# SUP_2_5_FMC.net
KiCad netlist of a schematic drawn in Altium Designer
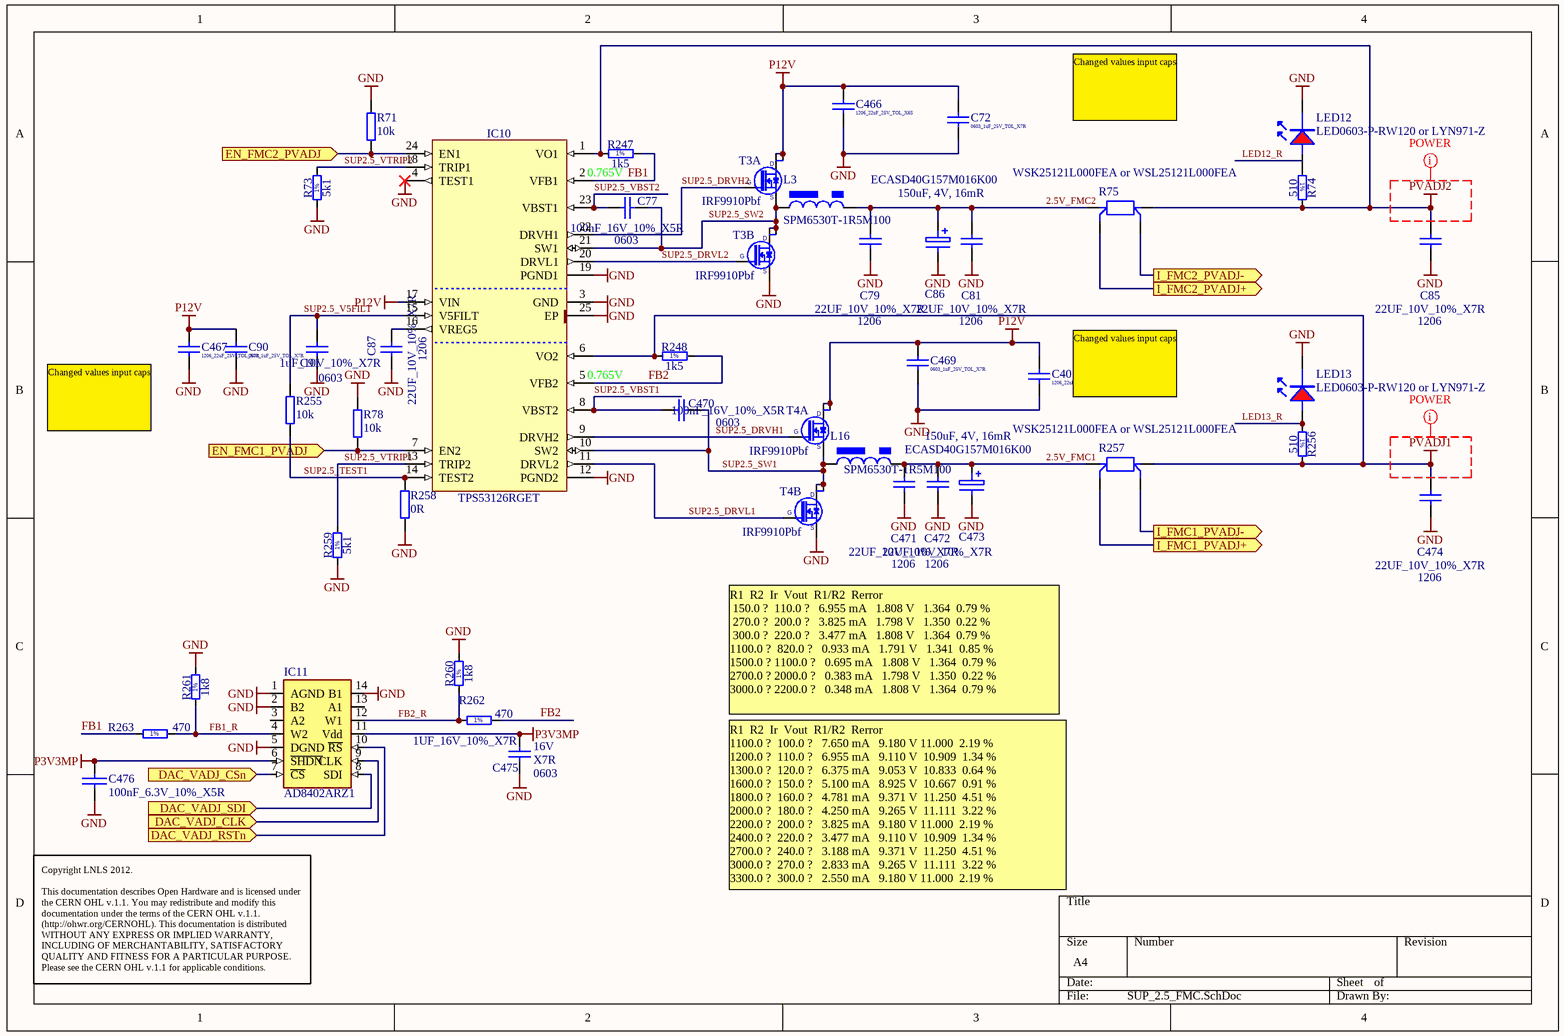
[diagram p0: SUP_2.5_FMC.SchDoc]

(export (version "E")
  (design (tool "Eeschema 10.0.6"))
  (components
    (comp (ref "C40")
      (value "1206_22uF_25V_TOL_X6S")
      (footprint "CAPC3225X140N")
      (fields (field (name "PART NUMBER") "Ceramic_1206"))
      (libsource (lib "Capacitors") (part "Capacitor"))
    )
    (comp (ref "C72")
      (value "0603_1uF_25V_TOL_X7R")
      (footprint "CAPC1608X90N")
      (fields (field (name "PART NUMBER") "Ceramic_0603"))
      (libsource (lib "Capacitors") (part "Capacitor"))
    )
    (comp (ref "C77")
      (value "100nF_16V_10%_X5R")
      (footprint "0402C")
      (description "Non-polarised capacitor")
      (fields
        (field (name "PART NUMBER") "CC0603_100NF_50V_10%_X7R")
        (field (name "VOLTAGE") "50V")
        (field (name "CASE") "0603")
        (field (name "AUTHOR") "CERN DEM JLC")
      )
      (libsource (lib "Capacitors") (part "Capacitor - non polarized"))
    )
    (comp (ref "C79")
      (value "22UF_10V_10%_X7R")
      (footprint "1206C")
      (description "Non-polarised capacitor")
      (fields
        (field (name "PART NUMBER") "CC1206_22UF_10V_10%_X7R")
        (field (name "VOLTAGE") "10V")
        (field (name "CASE") "1206")
        (field (name "AUTHOR") "CERN DEM JLC")
      )
      (libsource (lib "Capacitors") (part "Capacitor - non polarized"))
    )
    (comp (ref "C81")
      (value "22UF_10V_10%_X7R")
      (footprint "1206C")
      (description "Non-polarised capacitor")
      (fields
        (field (name "PART NUMBER") "CC1206_22UF_10V_10%_X7R")
        (field (name "VOLTAGE") "10V")
        (field (name "CASE") "1206")
        (field (name "AUTHOR") "CERN DEM JLC")
      )
      (libsource (lib "Capacitors") (part "Capacitor - non polarized"))
    )
    (comp (ref "C85")
      (value "22UF_10V_10%_X7R")
      (footprint "1206C")
      (description "Non-polarised capacitor")
      (fields
        (field (name "PART NUMBER") "CC1206_22UF_10V_10%_X7R")
        (field (name "VOLTAGE") "10V")
        (field (name "CASE") "1206")
        (field (name "AUTHOR") "CERN DEM JLC")
      )
      (libsource (lib "Capacitors") (part "Capacitor - non polarized"))
    )
    (comp (ref "C86")
      (value "ECASD40G157M016K00")
      (footprint "2917_POLY")
      (description "POLY, 150uF, 4V, ESR: 16mR")
      (fields (field (name "ALTIUM_VALUE") "150uF, 4V, 16mR"))
      (libsource (lib "LIBRARY_SCH") (part "CAP_POLYMER_SMDD"))
    )
    (comp (ref "C87")
      (value "22UF_10V_10%_X7R")
      (footprint "1206C")
      (description "Non-polarised capacitor")
      (fields
        (field (name "PART NUMBER") "CC1206_22UF_10V_10%_X7R")
        (field (name "VOLTAGE") "10V")
        (field (name "CASE") "1206")
        (field (name "AUTHOR") "CERN DEM JLC")
      )
      (libsource (lib "Capacitors") (part "Capacitor - non polarized"))
    )
    (comp (ref "C90")
      (value "0603_1uF_25V_TOL_X7R")
      (footprint "CAPC1608X90N")
      (fields (field (name "PART NUMBER") "Ceramic_0603"))
      (libsource (lib "Capacitors") (part "Capacitor"))
    )
    (comp (ref "C91")
      (value "1uF_10V_10%_X7R")
      (footprint "0603C")
      (description "Non-polarised capacitor")
      (fields
        (field (name "PART NUMBER") "CC0603_1UF_16V_10%_X7R")
        (field (name "VOLTAGE") "16V")
        (field (name "CASE") "0603")
        (field (name "AUTHOR") "CERN DEM JLC")
      )
      (libsource (lib "Capacitors") (part "Capacitor - non polarized"))
    )
    (comp (ref "C466")
      (value "1206_22uF_25V_TOL_X6S")
      (footprint "CAPC3225X140N")
      (fields (field (name "PART NUMBER") "Ceramic_1206"))
      (libsource (lib "Capacitors") (part "Capacitor"))
    )
    (comp (ref "C467")
      (value "1206_22uF_25V_TOL_X7R")
      (footprint "CAPC3225X140N")
      (fields (field (name "PART NUMBER") "Ceramic_1206"))
      (libsource (lib "Capacitors") (part "Capacitor"))
    )
    (comp (ref "C469")
      (value "0603_1uF_25V_TOL_X7R")
      (footprint "CAPC1608X90N")
      (fields (field (name "PART NUMBER") "Ceramic_0603"))
      (libsource (lib "Capacitors") (part "Capacitor"))
    )
    (comp (ref "C470")
      (value "100nF_16V_10%_X5R")
      (footprint "0402C")
      (description "Non-polarised capacitor")
      (fields
        (field (name "PART NUMBER") "CC0603_100NF_50V_10%_X7R")
        (field (name "VOLTAGE") "50V")
        (field (name "CASE") "0603")
        (field (name "AUTHOR") "CERN DEM JLC")
      )
      (libsource (lib "Capacitors") (part "Capacitor - non polarized"))
    )
    (comp (ref "C471")
      (value "22UF_10V_10%_X7R")
      (footprint "1206C")
      (description "Non-polarised capacitor")
      (fields
        (field (name "PART NUMBER") "CC1206_22UF_10V_10%_X7R")
        (field (name "VOLTAGE") "10V")
        (field (name "CASE") "1206")
        (field (name "AUTHOR") "CERN DEM JLC")
      )
      (libsource (lib "Capacitors") (part "Capacitor - non polarized"))
    )
    (comp (ref "C472")
      (value "22UF_10V_10%_X7R")
      (footprint "1206C")
      (description "Non-polarised capacitor")
      (fields
        (field (name "PART NUMBER") "CC1206_22UF_10V_10%_X7R")
        (field (name "VOLTAGE") "10V")
        (field (name "CASE") "1206")
        (field (name "AUTHOR") "CERN DEM JLC")
      )
      (libsource (lib "Capacitors") (part "Capacitor - non polarized"))
    )
    (comp (ref "C473")
      (value "ECASD40G157M016K00")
      (footprint "2917_POLY")
      (description "POLY, 150uF, 4V, ESR: 16mR")
      (fields (field (name "ALTIUM_VALUE") "150uF, 4V, 16mR"))
      (libsource (lib "LIBRARY_SCH") (part "CAP_POLYMER_SMDD"))
    )
    (comp (ref "C474")
      (value "22UF_10V_10%_X7R")
      (footprint "1206C")
      (description "Non-polarised capacitor")
      (fields
        (field (name "PART NUMBER") "CC1206_22UF_10V_10%_X7R")
        (field (name "VOLTAGE") "10V")
        (field (name "CASE") "1206")
        (field (name "AUTHOR") "CERN DEM JLC")
      )
      (libsource (lib "Capacitors") (part "Capacitor - non polarized"))
    )
    (comp (ref "C475")
      (value "1UF_16V_10%_X7R")
      (footprint "0603C")
      (description "Non-polarised capacitor")
      (fields
        (field (name "PART NUMBER") "CC0603_1UF_16V_10%_X7R")
        (field (name "VOLTAGE") "16V")
        (field (name "TC") "X7R")
        (field (name "TOLERANCE") "±10%")
        (field (name "CASE") "0603")
        (field (name "AUTHOR") "CERN DEM JLC")
      )
      (libsource (lib "Capacitors") (part "Capacitor - non polarized"))
    )
    (comp (ref "C476")
      (value "100nF_6.3V_10%_X5R")
      (footprint "0201C")
      (description "Capacitor SMD")
      (libsource (lib "LIBRARY_SCH") (part "CAP_SMD_0201"))
    )
    (comp (ref "IC10")
      (value "TPS53126RGET")
      (footprint "QFN50P400X400X100-25N-S255")
      (description "Dual Synchronous Step-Down Controller For Low Voltage Power Rails")
      (fields (field (name "MANUFACTURER") "TEXAS INSTRUMENTS") (field (name "AUTHOR") "CERN DEM JLC"))
      (libsource (lib "ICs And Semiconductors") (part "TPS53126RGET"))
    )
    (comp (ref "IC11")
      (value "AD8402ARZ1")
      (footprint "SO-14")
      (description "1k dual digital potentiometer")
      (libsource (lib "LIBRARY_SCH") (part "DAC_AD8402"))
    )
    (comp (ref "L3")
      (value "SPM6530T-1R5M100")
      (footprint "IND_TDK_SPM6530")
      (description "1.5uH, 20%, 10mR, 11.5A")
      (libsource (lib "LIBRARY_SCH") (part "L_POWER_SPM6530T"))
    )
    (comp (ref "L16")
      (value "SPM6530T-1R5M100")
      (footprint "IND_TDK_SPM6530")
      (description "1.5uH, 20%, 10mR, 11.5A")
      (libsource (lib "LIBRARY_SCH") (part "L_POWER_SPM6530T"))
    )
    (comp (ref "LED12")
      (value "LED0603-P-RW120 or LYN971-Z")
      (footprint "led_0603R")
      (description "LED 0603 red")
      (libsource (lib "LIBRARY_SCH") (part "LED_0603R"))
    )
    (comp (ref "LED13")
      (value "LED0603-P-RW120 or LYN971-Z")
      (footprint "led_0603R")
      (description "LED 0603 red")
      (libsource (lib "LIBRARY_SCH") (part "LED_0603R"))
    )
    (comp (ref "R71")
      (value "10k")
      (footprint "0402R")
      (description "SMD Resistor")
      (libsource (lib "LIBRARY_SCH") (part "RES_0402"))
    )
    (comp (ref "R73")
      (value "5k1")
      (footprint "0603R")
      (description "Resistor - 1%")
      (fields
        (field (name "PART NUMBER") "R0603_5K1_1%_0.1W_100PPM")
        (field (name "POWER") "0.1W")
        (field (name "AUTHOR") "CERN DEM JLC")
      )
      (libsource (lib "Resistors") (part "Resistor - 1%"))
    )
    (comp (ref "R74")
      (value "510")
      (footprint "0603R")
      (description "Resistor - 1%")
      (fields
        (field (name "PART NUMBER") "R0402_510R_1%_0.0625W_100PPM")
        (field (name "POWER") "0.0625W")
        (field (name "AUTHOR") "CERN DEM JLC")
      )
      (libsource (lib "Resistors") (part "Resistor - 1%"))
    )
    (comp (ref "R75")
      (value "WSK25121L000FEA or WSL25121L000FEA")
      (footprint "RES_WSK2512")
      (description "RESISTOR, METAL STRIP, 0.001 OHM 1%")
      (libsource (lib "LIBRARY_SCH") (part "RES_POW_Kelvin"))
    )
    (comp (ref "R78")
      (value "10k")
      (footprint "0402R")
      (description "SMD Resistor")
      (libsource (lib "LIBRARY_SCH") (part "RES_0402"))
    )
    (comp (ref "R247")
      (value "1k5")
      (footprint "RESC1608X55N")
      (description "Resistor - 1%")
      (fields
        (field (name "PART NUMBER") "R0603_1K5_1%_0.1W_100PPM")
        (field (name "POWER") "0.1W")
        (field (name "AUTHOR") "CERN DEM JLC")
      )
      (libsource (lib "Resistors") (part "Resistor - 1%"))
    )
    (comp (ref "R248")
      (value "1k5")
      (footprint "RESC1608X55N")
      (description "Resistor - 1%")
      (fields
        (field (name "PART NUMBER") "R0603_1K5_1%_0.1W_100PPM")
        (field (name "POWER") "0.1W")
        (field (name "AUTHOR") "CERN DEM JLC")
      )
      (libsource (lib "Resistors") (part "Resistor - 1%"))
    )
    (comp (ref "R255")
      (value "10k")
      (footprint "0402R")
      (description "SMD Resistor")
      (libsource (lib "LIBRARY_SCH") (part "RES_0402"))
    )
    (comp (ref "R256")
      (value "510")
      (footprint "0603R")
      (description "Resistor - 1%")
      (fields
        (field (name "PART NUMBER") "R0402_510R_1%_0.0625W_100PPM")
        (field (name "POWER") "0.0625W")
        (field (name "AUTHOR") "CERN DEM JLC")
      )
      (libsource (lib "Resistors") (part "Resistor - 1%"))
    )
    (comp (ref "R257")
      (value "WSK25121L000FEA or WSL25121L000FEA")
      (footprint "RES_WSK2512")
      (description "RESISTOR, METAL STRIP, 0.001 OHM 1%")
      (libsource (lib "LIBRARY_SCH") (part "RES_POW_Kelvin"))
    )
    (comp (ref "R258")
      (value "0R")
      (footprint "0402R")
      (description "SMD Resistor")
      (libsource (lib "LIBRARY_SCH") (part "RES_0402"))
    )
    (comp (ref "R259")
      (value "5k1")
      (footprint "0603R")
      (description "Resistor - 1%")
      (fields
        (field (name "PART NUMBER") "R0603_5K1_1%_0.1W_100PPM")
        (field (name "POWER") "0.1W")
        (field (name "AUTHOR") "CERN DEM JLC")
      )
      (libsource (lib "Resistors") (part "Resistor - 1%"))
    )
    (comp (ref "R260")
      (value "1k8")
      (footprint "RESC1608X55N")
      (description "Resistor - 1%")
      (fields
        (field (name "PART NUMBER") "R0603_910R_1%_0.1W_100PPM")
        (field (name "POWER") "0.1W")
        (field (name "AUTHOR") "CERN DEM JLC")
      )
      (libsource (lib "Resistors") (part "Resistor - 1%"))
    )
    (comp (ref "R261")
      (value "1k8")
      (footprint "RESC1608X55N")
      (description "Resistor - 1%")
      (fields
        (field (name "PART NUMBER") "R0603_910R_1%_0.1W_100PPM")
        (field (name "POWER") "0.1W")
        (field (name "AUTHOR") "CERN DEM JLC")
      )
      (libsource (lib "Resistors") (part "Resistor - 1%"))
    )
    (comp (ref "R262")
      (value "470")
      (footprint "RESC1608X55N")
      (description "Resistor - 1%")
      (fields
        (field (name "PART NUMBER") "R0603_470R_1%_0.1W_100PPM")
        (field (name "POWER") "0.1W")
        (field (name "AUTHOR") "CERN DEM JLC")
      )
      (libsource (lib "Resistors") (part "Resistor - 1%"))
    )
    (comp (ref "R263")
      (value "470")
      (footprint "RESC1608X55N")
      (description "Resistor - 1%")
      (fields
        (field (name "PART NUMBER") "R0603_470R_1%_0.1W_100PPM")
        (field (name "POWER") "0.1W")
        (field (name "AUTHOR") "CERN DEM JLC")
      )
      (libsource (lib "Resistors") (part "Resistor - 1%"))
    )
    (comp (ref "T3")
      (value "IRF9910Pbf")
      (footprint "SOIC127P600X175-8N")
      (description "Dual SO-8 MOSFET For POL Cconverter")
      (fields (field (name "MANUFACTURER") "INTERNATIONAL RECTIFIER") (field (name "AUTHOR") "CERN DEM JLC"))
      (libsource (lib "ICs And Semiconductors") (part "IRF9910"))
    )
    (comp (ref "T4")
      (value "IRF9910Pbf")
      (footprint "SOIC127P600X175-8N")
      (description "Dual SO-8 MOSFET For POL Cconverter")
      (fields (field (name "MANUFACTURER") "INTERNATIONAL RECTIFIER") (field (name "AUTHOR") "CERN DEM JLC"))
      (libsource (lib "ICs And Semiconductors") (part "IRF9910"))
    )
  )
  (nets
    (net (code "1") (name "/2.5V_FMC1") (class "Default")
      (node (ref "C471") (pin "1") (pinfunction "1_1") (pintype "passive"))
      (node (ref "C472") (pin "1") (pinfunction "1_1") (pintype "passive"))
      (node (ref "C473") (pin "1") (pinfunction "1_1") (pintype "passive"))
      (node (ref "L16") (pin "2") (pintype "passive"))
      (node (ref "R257") (pin "1") (pinfunction "1_1") (pintype "passive"))
    )
    (net (code "2") (name "/2.5V_FMC2") (class "Default")
      (node (ref "C79") (pin "1") (pinfunction "1_1") (pintype "passive"))
      (node (ref "C81") (pin "1") (pinfunction "1_1") (pintype "passive"))
      (node (ref "C86") (pin "1") (pinfunction "1_1") (pintype "passive"))
      (node (ref "L3") (pin "2") (pintype "passive"))
      (node (ref "R75") (pin "1") (pinfunction "1_1") (pintype "passive"))
    )
    (net (code "3") (name "/DAC_VADJ_CLK") (class "Default")
      (node (ref "IC11") (pin "9") (pinfunction "CLK_9") (pintype "input"))
    )
    (net (code "4") (name "/DAC_VADJ_CSn") (class "Default")
      (node (ref "IC11") (pin "7") (pinfunction "~{CS}_7") (pintype "input"))
    )
    (net (code "5") (name "/DAC_VADJ_RSTn") (class "Default")
      (node (ref "IC11") (pin "10") (pinfunction "~{RS}_10") (pintype "input"))
    )
    (net (code "6") (name "/DAC_VADJ_SDI") (class "Default")
      (node (ref "IC11") (pin "8") (pinfunction "SDI_8") (pintype "input"))
    )
    (net (code "7") (name "/EN_FMC1_PVADJ") (class "Default")
      (node (ref "IC10") (pin "7") (pinfunction "EN2_7") (pintype "input"))
      (node (ref "R78") (pin "1") (pinfunction "1_1") (pintype "passive"))
    )
    (net (code "8") (name "/EN_FMC2_PVADJ") (class "Default")
      (node (ref "IC10") (pin "24") (pinfunction "EN1_24") (pintype "input"))
      (node (ref "R71") (pin "1") (pinfunction "1_1") (pintype "passive"))
    )
    (net (code "9") (name "/FB1") (class "Default")
      (node (ref "IC10") (pin "2") (pinfunction "VFB1_2") (pintype "input"))
      (node (ref "R247") (pin "2") (pinfunction "2_2") (pintype "passive"))
      (node (ref "R263") (pin "1") (pinfunction "1_1") (pintype "passive"))
    )
    (net (code "10") (name "/FB1_R") (class "Default")
      (node (ref "IC11") (pin "4") (pinfunction "W2_4") (pintype "passive"))
      (node (ref "R261") (pin "1") (pinfunction "1_1") (pintype "passive"))
      (node (ref "R263") (pin "2") (pinfunction "2_2") (pintype "passive"))
    )
    (net (code "11") (name "/FB2") (class "Default")
      (node (ref "IC10") (pin "5") (pinfunction "VFB2_5") (pintype "input"))
      (node (ref "R248") (pin "2") (pinfunction "2_2") (pintype "passive"))
      (node (ref "R262") (pin "2") (pinfunction "2_2") (pintype "passive"))
    )
    (net (code "12") (name "/FB2_R") (class "Default")
      (node (ref "IC11") (pin "12") (pinfunction "W1_12") (pintype "passive"))
      (node (ref "R260") (pin "1") (pinfunction "1_1") (pintype "passive"))
      (node (ref "R262") (pin "1") (pinfunction "1_1") (pintype "passive"))
    )
    (net (code "13") (name "/I_FMC1_PVADJ+") (class "Default")
      (node (ref "R257") (pin "1a") (pinfunction "1a_1a") (pintype "passive"))
    )
    (net (code "14") (name "/I_FMC1_PVADJ-") (class "Default")
      (node (ref "R257") (pin "2a") (pinfunction "2a_2a") (pintype "passive"))
    )
    (net (code "15") (name "/I_FMC2_PVADJ+") (class "Default")
      (node (ref "R75") (pin "1a") (pinfunction "1a_1a") (pintype "passive"))
    )
    (net (code "16") (name "/I_FMC2_PVADJ-") (class "Default")
      (node (ref "R75") (pin "2a") (pinfunction "2a_2a") (pintype "passive"))
    )
    (net (code "18") (name "/LED13_R") (class "Default")
      (node (ref "LED13") (pin "A") (pinfunction "A_A") (pintype "passive"))
      (node (ref "R256") (pin "1") (pinfunction "1_1") (pintype "passive"))
    )
    (net (code "19") (name "/SUP2.5_DRVH1") (class "Default")
      (node (ref "IC10") (pin "9") (pinfunction "DRVH2_9") (pintype "output"))
      (node (ref "T4") (pin "4") (pinfunction "G_4") (pintype "passive"))
    )
    (net (code "20") (name "/SUP2.5_DRVH2") (class "Default")
      (node (ref "IC10") (pin "22") (pinfunction "DRVH1_22") (pintype "output"))
      (node (ref "T3") (pin "4") (pinfunction "G_4") (pintype "passive"))
    )
    (net (code "21") (name "/SUP2.5_DRVL1") (class "Default")
      (node (ref "IC10") (pin "11") (pinfunction "DRVL2_11") (pintype "output"))
      (node (ref "T4") (pin "2") (pinfunction "G_2") (pintype "passive"))
    )
    (net (code "22") (name "/SUP2.5_DRVL2") (class "Default")
      (node (ref "IC10") (pin "20") (pinfunction "DRVL1_20") (pintype "output"))
      (node (ref "T3") (pin "2") (pinfunction "G_2") (pintype "passive"))
    )
    (net (code "23") (name "/SUP2.5_SW1") (class "Default")
      (node (ref "C470") (pin "1") (pinfunction "1_1") (pintype "passive"))
      (node (ref "IC10") (pin "10") (pinfunction "SW2_10") (pintype "bidirectional"))
      (node (ref "L16") (pin "1") (pintype "passive"))
      (node (ref "T4") (pin "3") (pinfunction "S_3") (pintype "passive"))
      (node (ref "T4") (pin "7") (pinfunction "D_7") (pintype "passive"))
      (node (ref "T4") (pin "8") (pinfunction "D_8") (pintype "passive"))
    )
    (net (code "24") (name "/SUP2.5_SW2") (class "Default")
      (node (ref "C77") (pin "1") (pinfunction "1_1") (pintype "passive"))
      (node (ref "IC10") (pin "21") (pinfunction "SW1_21") (pintype "bidirectional"))
      (node (ref "L3") (pin "1") (pintype "passive"))
      (node (ref "T3") (pin "3") (pinfunction "S_3") (pintype "passive"))
      (node (ref "T3") (pin "7") (pinfunction "D_7") (pintype "passive"))
      (node (ref "T3") (pin "8") (pinfunction "D_8") (pintype "passive"))
    )
    (net (code "25") (name "/SUP2.5_TEST1") (class "Default")
      (node (ref "IC10") (pin "14") (pinfunction "TEST2_14") (pintype "input"))
      (node (ref "R255") (pin "1") (pinfunction "1_1") (pintype "passive"))
      (node (ref "R258") (pin "2") (pinfunction "2_2") (pintype "passive"))
    )
    (net (code "26") (name "/SUP2.5_V5FILT") (class "Default")
      (node (ref "C91") (pin "2") (pinfunction "2_2") (pintype "passive"))
      (node (ref "IC10") (pin "15") (pinfunction "V5FILT_15") (pintype "input"))
      (node (ref "R255") (pin "2") (pinfunction "2_2") (pintype "passive"))
    )
    (net (code "27") (name "/SUP2.5_VBST1") (class "Default")
      (node (ref "C470") (pin "2") (pinfunction "2_2") (pintype "passive"))
      (node (ref "IC10") (pin "8") (pinfunction "VBST2_8") (pintype "input"))
    )
    (net (code "28") (name "/SUP2.5_VBST2") (class "Default")
      (node (ref "C77") (pin "2") (pinfunction "2_2") (pintype "passive"))
      (node (ref "IC10") (pin "23") (pinfunction "VBST1_23") (pintype "input"))
    )
    (net (code "29") (name "/SUP2.5_VTRIP1") (class "Default")
      (node (ref "IC10") (pin "13") (pinfunction "TRIP2_13") (pintype "input"))
      (node (ref "R259") (pin "2") (pinfunction "2_2") (pintype "passive"))
    )
    (net (code "30") (name "/SUP2.5_VTRIP2") (class "Default")
      (node (ref "IC10") (pin "18") (pinfunction "TRIP1_18") (pintype "input"))
      (node (ref "R73") (pin "2") (pinfunction "2_2") (pintype "passive"))
    )
    (net (code "31") (name "GND") (class "Default")
      (node (ref "C40") (pin "1") (pinfunction "1_1") (pintype "passive"))
      (node (ref "C466") (pin "1") (pinfunction "1_1") (pintype "passive"))
      (node (ref "C467") (pin "1") (pinfunction "1_1") (pintype "passive"))
      (node (ref "C469") (pin "1") (pinfunction "1_1") (pintype "passive"))
      (node (ref "C471") (pin "2") (pinfunction "2_2") (pintype "passive"))
      (node (ref "C472") (pin "2") (pinfunction "2_2") (pintype "passive"))
      (node (ref "C473") (pin "2") (pinfunction "2_2") (pintype "passive"))
      (node (ref "C474") (pin "2") (pinfunction "2_2") (pintype "passive"))
      (node (ref "C475") (pin "1") (pinfunction "1_1") (pintype "passive"))
      (node (ref "C476") (pin "2") (pinfunction "2_2") (pintype "passive"))
      (node (ref "C72") (pin "1") (pinfunction "1_1") (pintype "passive"))
      (node (ref "C79") (pin "2") (pinfunction "2_2") (pintype "passive"))
      (node (ref "C81") (pin "2") (pinfunction "2_2") (pintype "passive"))
      (node (ref "C85") (pin "2") (pinfunction "2_2") (pintype "passive"))
      (node (ref "C86") (pin "2") (pinfunction "2_2") (pintype "passive"))
      (node (ref "C87") (pin "1") (pinfunction "1_1") (pintype "passive"))
      (node (ref "C90") (pin "1") (pinfunction "1_1") (pintype "passive"))
      (node (ref "C91") (pin "1") (pinfunction "1_1") (pintype "passive"))
      (node (ref "IC10") (pin "12") (pinfunction "PGND2_12") (pintype "power_in"))
      (node (ref "IC10") (pin "19") (pinfunction "PGND1_19") (pintype "power_in"))
      (node (ref "IC10") (pin "25") (pinfunction "EP_25") (pintype "power_in"))
      (node (ref "IC10") (pin "3") (pinfunction "GND_3") (pintype "power_in"))
      (node (ref "IC10") (pin "4") (pinfunction "TEST1_4") (pintype "output"))
      (node (ref "IC11") (pin "1") (pinfunction "AGND_1") (pintype "power_in"))
      (node (ref "IC11") (pin "14") (pinfunction "B1_14") (pintype "passive"))
      (node (ref "IC11") (pin "2") (pinfunction "B2_2") (pintype "passive"))
      (node (ref "IC11") (pin "5") (pinfunction "DGND_5") (pintype "power_in"))
      (node (ref "LED12") (pin "K") (pinfunction "K_K") (pintype "passive"))
      (node (ref "LED13") (pin "K") (pinfunction "K_K") (pintype "passive"))
      (node (ref "R258") (pin "1") (pinfunction "1_1") (pintype "passive"))
      (node (ref "R259") (pin "1") (pinfunction "1_1") (pintype "passive"))
      (node (ref "R260") (pin "2") (pinfunction "2_2") (pintype "passive"))
      (node (ref "R261") (pin "2") (pinfunction "2_2") (pintype "passive"))
      (node (ref "R71") (pin "2") (pinfunction "2_2") (pintype "passive"))
      (node (ref "R73") (pin "1") (pinfunction "1_1") (pintype "passive"))
      (node (ref "R78") (pin "2") (pinfunction "2_2") (pintype "passive"))
      (node (ref "T3") (pin "1") (pinfunction "S_1") (pintype "passive"))
      (node (ref "T4") (pin "1") (pinfunction "S_1") (pintype "passive"))
    )
    (net (code "32") (name "Net-(IC10-VREG5)") (class "Default")
      (node (ref "C87") (pin "2") (pinfunction "2_2") (pintype "passive"))
      (node (ref "IC10") (pin "16") (pinfunction "VREG5_16") (pintype "output"))
    )
    (net (code "33") (name "Net-(LED12-PadA)") (class "Default")
      (node (ref "LED12") (pin "A") (pinfunction "A_A") (pintype "passive"))
      (node (ref "R74") (pin "1") (pinfunction "1_1") (pintype "passive"))
    )
    (net (code "34") (name "P3V3MP") (class "Default")
      (node (ref "C475") (pin "2") (pinfunction "2_2") (pintype "passive"))
      (node (ref "C476") (pin "1") (pinfunction "1_1") (pintype "passive"))
      (node (ref "IC11") (pin "11") (pinfunction "Vdd_11") (pintype "power_in"))
      (node (ref "IC11") (pin "6") (pinfunction "~{SHDN}_6") (pintype "input"))
    )
    (net (code "35") (name "P12V") (class "Default")
      (node (ref "C40") (pin "2") (pinfunction "2_2") (pintype "passive"))
      (node (ref "C466") (pin "2") (pinfunction "2_2") (pintype "passive"))
      (node (ref "C467") (pin "2") (pinfunction "2_2") (pintype "passive"))
      (node (ref "C469") (pin "2") (pinfunction "2_2") (pintype "passive"))
      (node (ref "C72") (pin "2") (pinfunction "2_2") (pintype "passive"))
      (node (ref "C90") (pin "2") (pinfunction "2_2") (pintype "passive"))
      (node (ref "IC10") (pin "17") (pinfunction "VIN_17") (pintype "input"))
      (node (ref "T3") (pin "5") (pinfunction "D_5") (pintype "passive"))
      (node (ref "T3") (pin "6") (pinfunction "D_6") (pintype "passive"))
      (node (ref "T4") (pin "5") (pinfunction "D_5") (pintype "passive"))
      (node (ref "T4") (pin "6") (pinfunction "D_6") (pintype "passive"))
    )
    (net (code "36") (name "PVADJ1") (class "Default")
      (node (ref "C474") (pin "1") (pinfunction "1_1") (pintype "passive"))
      (node (ref "IC10") (pin "6") (pinfunction "VO2_6") (pintype "input"))
      (node (ref "R248") (pin "1") (pinfunction "1_1") (pintype "passive"))
      (node (ref "R256") (pin "2") (pinfunction "2_2") (pintype "passive"))
      (node (ref "R257") (pin "2") (pinfunction "2_2") (pintype "passive"))
    )
    (net (code "37") (name "PVADJ2") (class "Default")
      (node (ref "C85") (pin "1") (pinfunction "1_1") (pintype "passive"))
      (node (ref "IC10") (pin "1") (pinfunction "VO1_1") (pintype "input"))
      (node (ref "R247") (pin "1") (pinfunction "1_1") (pintype "passive"))
      (node (ref "R74") (pin "2") (pinfunction "2_2") (pintype "passive"))
      (node (ref "R75") (pin "2") (pinfunction "2_2") (pintype "passive"))
    )
    (net (code "38") (name "unconnected-(IC11-A1-Pad13)") (class "Default")
      (node (ref "IC11") (pin "13") (pinfunction "A1_13") (pintype "passive"))
    )
    (net (code "39") (name "unconnected-(IC11-A2-Pad3)") (class "Default")
      (node (ref "IC11") (pin "3") (pinfunction "A2_3") (pintype "passive"))
    )
  )
)
